# lisa_l_low_carrier.net
KiCad netlist of a schematic drawn in EAGLE
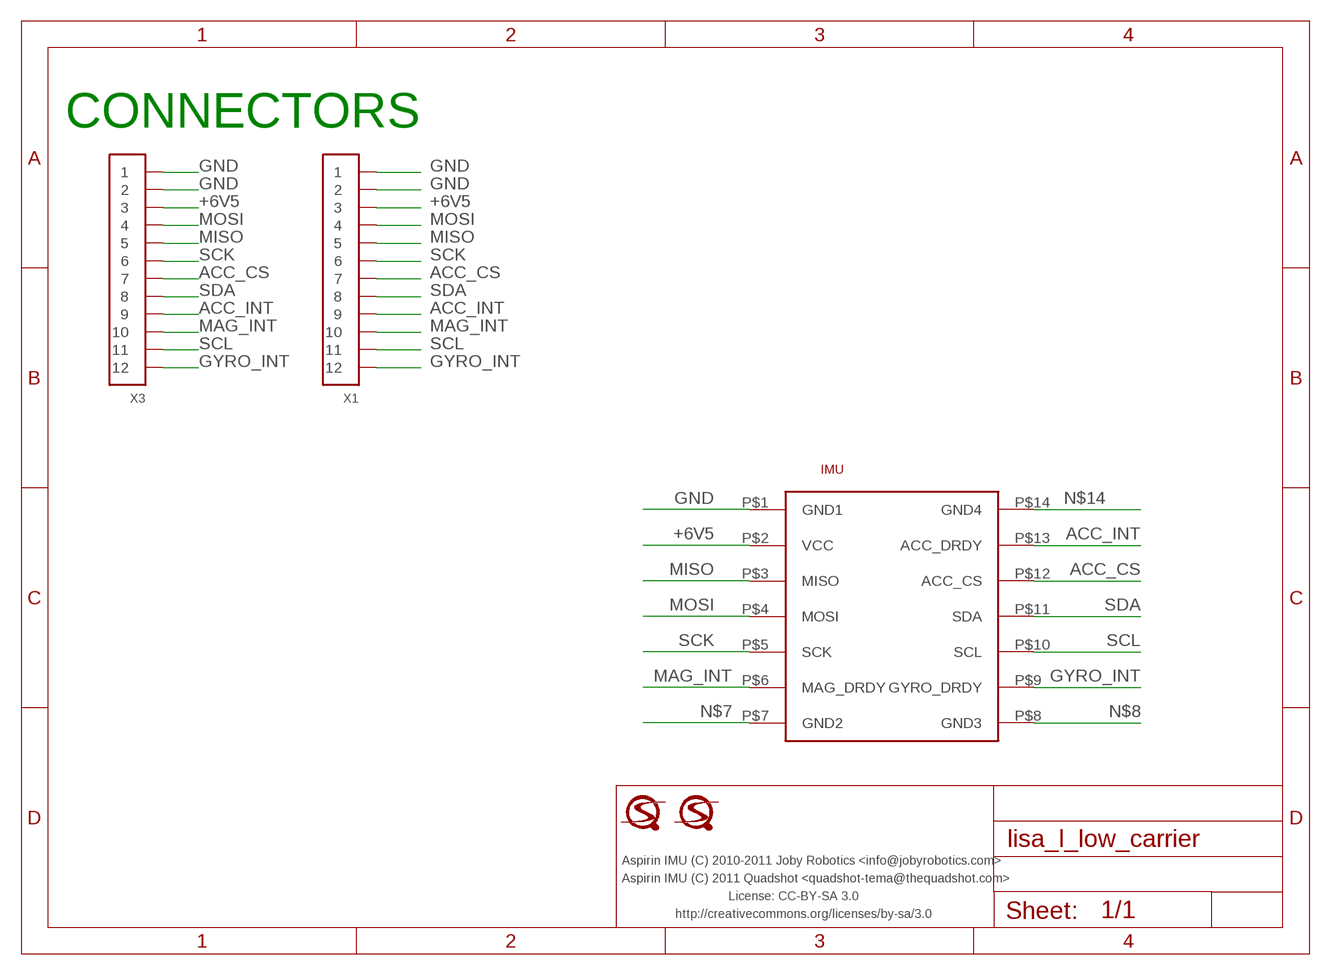
[diagram p0: schematic, sheet 1]

(export (version "E")
  (design (tool "Eeschema 10.0.6"))
  (components
    (comp (ref "IMU")
      (value "ASPIRIN")
      (footprint "eagle-import:ASPIRIN_1")
      (libsource (lib "eagle-import") (part "ASPIRIN"))
    )
    (comp (ref "U$1")
      (value "LOGO")
      (footprint "eagle-import:LOGO")
      (libsource (lib "eagle-import") (part "LOGO"))
    )
    (comp (ref "U$2")
      (value "LOGO")
      (footprint "eagle-import:LOGO")
      (libsource (lib "eagle-import") (part "LOGO"))
    )
    (comp (ref "X1")
      (value "CONN_12-1-53261")
      (footprint "eagle-import:PB-53261-12")
      (libsource (lib "eagle-import") (part "CONN_12-1-53261"))
    )
    (comp (ref "X3")
      (value "CONN_12-1-53047")
      (footprint "eagle-import:PB-53047-12")
      (libsource (lib "eagle-import") (part "CONN_12-1-53047"))
    )
  )
  (nets
    (net (code "1") (name "/+6V5") (class "Default")
      (node (ref "IMU") (pin "P$2") (pinfunction "VCC_P$2") (pintype "bidirectional"))
      (node (ref "X1") (pin "3") (pinfunction "3_3") (pintype "bidirectional"))
      (node (ref "X3") (pin "3") (pinfunction "3_3") (pintype "bidirectional"))
    )
    (net (code "2") (name "/ACC_CS") (class "Default")
      (node (ref "IMU") (pin "P$12") (pinfunction "ACC_CS_P$12") (pintype "bidirectional"))
      (node (ref "X1") (pin "7") (pinfunction "7_7") (pintype "bidirectional"))
      (node (ref "X3") (pin "7") (pinfunction "7_7") (pintype "bidirectional"))
    )
    (net (code "3") (name "/ACC_INT") (class "Default")
      (node (ref "IMU") (pin "P$13") (pinfunction "ACC_DRDY_P$13") (pintype "bidirectional"))
      (node (ref "X1") (pin "9") (pinfunction "9_9") (pintype "bidirectional"))
      (node (ref "X3") (pin "9") (pinfunction "9_9") (pintype "bidirectional"))
    )
    (net (code "4") (name "/GND") (class "Default")
      (node (ref "IMU") (pin "P$1") (pinfunction "GND1_P$1") (pintype "bidirectional"))
      (node (ref "X1") (pin "1") (pinfunction "1_1") (pintype "bidirectional"))
      (node (ref "X1") (pin "2") (pinfunction "2_2") (pintype "bidirectional"))
      (node (ref "X3") (pin "1") (pinfunction "1_1") (pintype "bidirectional"))
      (node (ref "X3") (pin "2") (pinfunction "2_2") (pintype "bidirectional"))
    )
    (net (code "5") (name "/GYRO_INT") (class "Default")
      (node (ref "IMU") (pin "P$9") (pinfunction "GYRO_DRDY_P$9") (pintype "bidirectional"))
      (node (ref "X1") (pin "12") (pinfunction "12_12") (pintype "bidirectional"))
      (node (ref "X3") (pin "12") (pinfunction "12_12") (pintype "bidirectional"))
    )
    (net (code "6") (name "/MAG_INT") (class "Default")
      (node (ref "IMU") (pin "P$6") (pinfunction "MAG_DRDY_P$6") (pintype "bidirectional"))
      (node (ref "X1") (pin "10") (pinfunction "10_10") (pintype "bidirectional"))
      (node (ref "X3") (pin "10") (pinfunction "10_10") (pintype "bidirectional"))
    )
    (net (code "7") (name "/MISO") (class "Default")
      (node (ref "IMU") (pin "P$3") (pinfunction "MISO_P$3") (pintype "bidirectional"))
      (node (ref "X1") (pin "5") (pinfunction "5_5") (pintype "bidirectional"))
      (node (ref "X3") (pin "5") (pinfunction "5_5") (pintype "bidirectional"))
    )
    (net (code "8") (name "/MOSI") (class "Default")
      (node (ref "IMU") (pin "P$4") (pinfunction "MOSI_P$4") (pintype "bidirectional"))
      (node (ref "X1") (pin "4") (pinfunction "4_4") (pintype "bidirectional"))
      (node (ref "X3") (pin "4") (pinfunction "4_4") (pintype "bidirectional"))
    )
    (net (code "9") (name "/N$7") (class "Default")
      (node (ref "IMU") (pin "P$7") (pinfunction "GND2_P$7") (pintype "bidirectional"))
    )
    (net (code "10") (name "/N$8") (class "Default")
      (node (ref "IMU") (pin "P$8") (pinfunction "GND3_P$8") (pintype "bidirectional"))
    )
    (net (code "11") (name "/N$14") (class "Default")
      (node (ref "IMU") (pin "P$14") (pinfunction "GND4_P$14") (pintype "bidirectional"))
    )
    (net (code "12") (name "/SCK") (class "Default")
      (node (ref "IMU") (pin "P$5") (pinfunction "SCK_P$5") (pintype "bidirectional"))
      (node (ref "X1") (pin "6") (pinfunction "6_6") (pintype "bidirectional"))
      (node (ref "X3") (pin "6") (pinfunction "6_6") (pintype "bidirectional"))
    )
    (net (code "13") (name "/SCL") (class "Default")
      (node (ref "IMU") (pin "P$10") (pinfunction "SCL_P$10") (pintype "bidirectional"))
      (node (ref "X1") (pin "11") (pinfunction "11_11") (pintype "bidirectional"))
      (node (ref "X3") (pin "11") (pinfunction "11_11") (pintype "bidirectional"))
    )
    (net (code "14") (name "/SDA") (class "Default")
      (node (ref "IMU") (pin "P$11") (pinfunction "SDA_P$11") (pintype "bidirectional"))
      (node (ref "X1") (pin "8") (pinfunction "8_8") (pintype "bidirectional"))
      (node (ref "X3") (pin "8") (pinfunction "8_8") (pintype "bidirectional"))
    )
  )
)
